# followers_v1.net
KiCad netlist of a schematic drawn in EAGLE
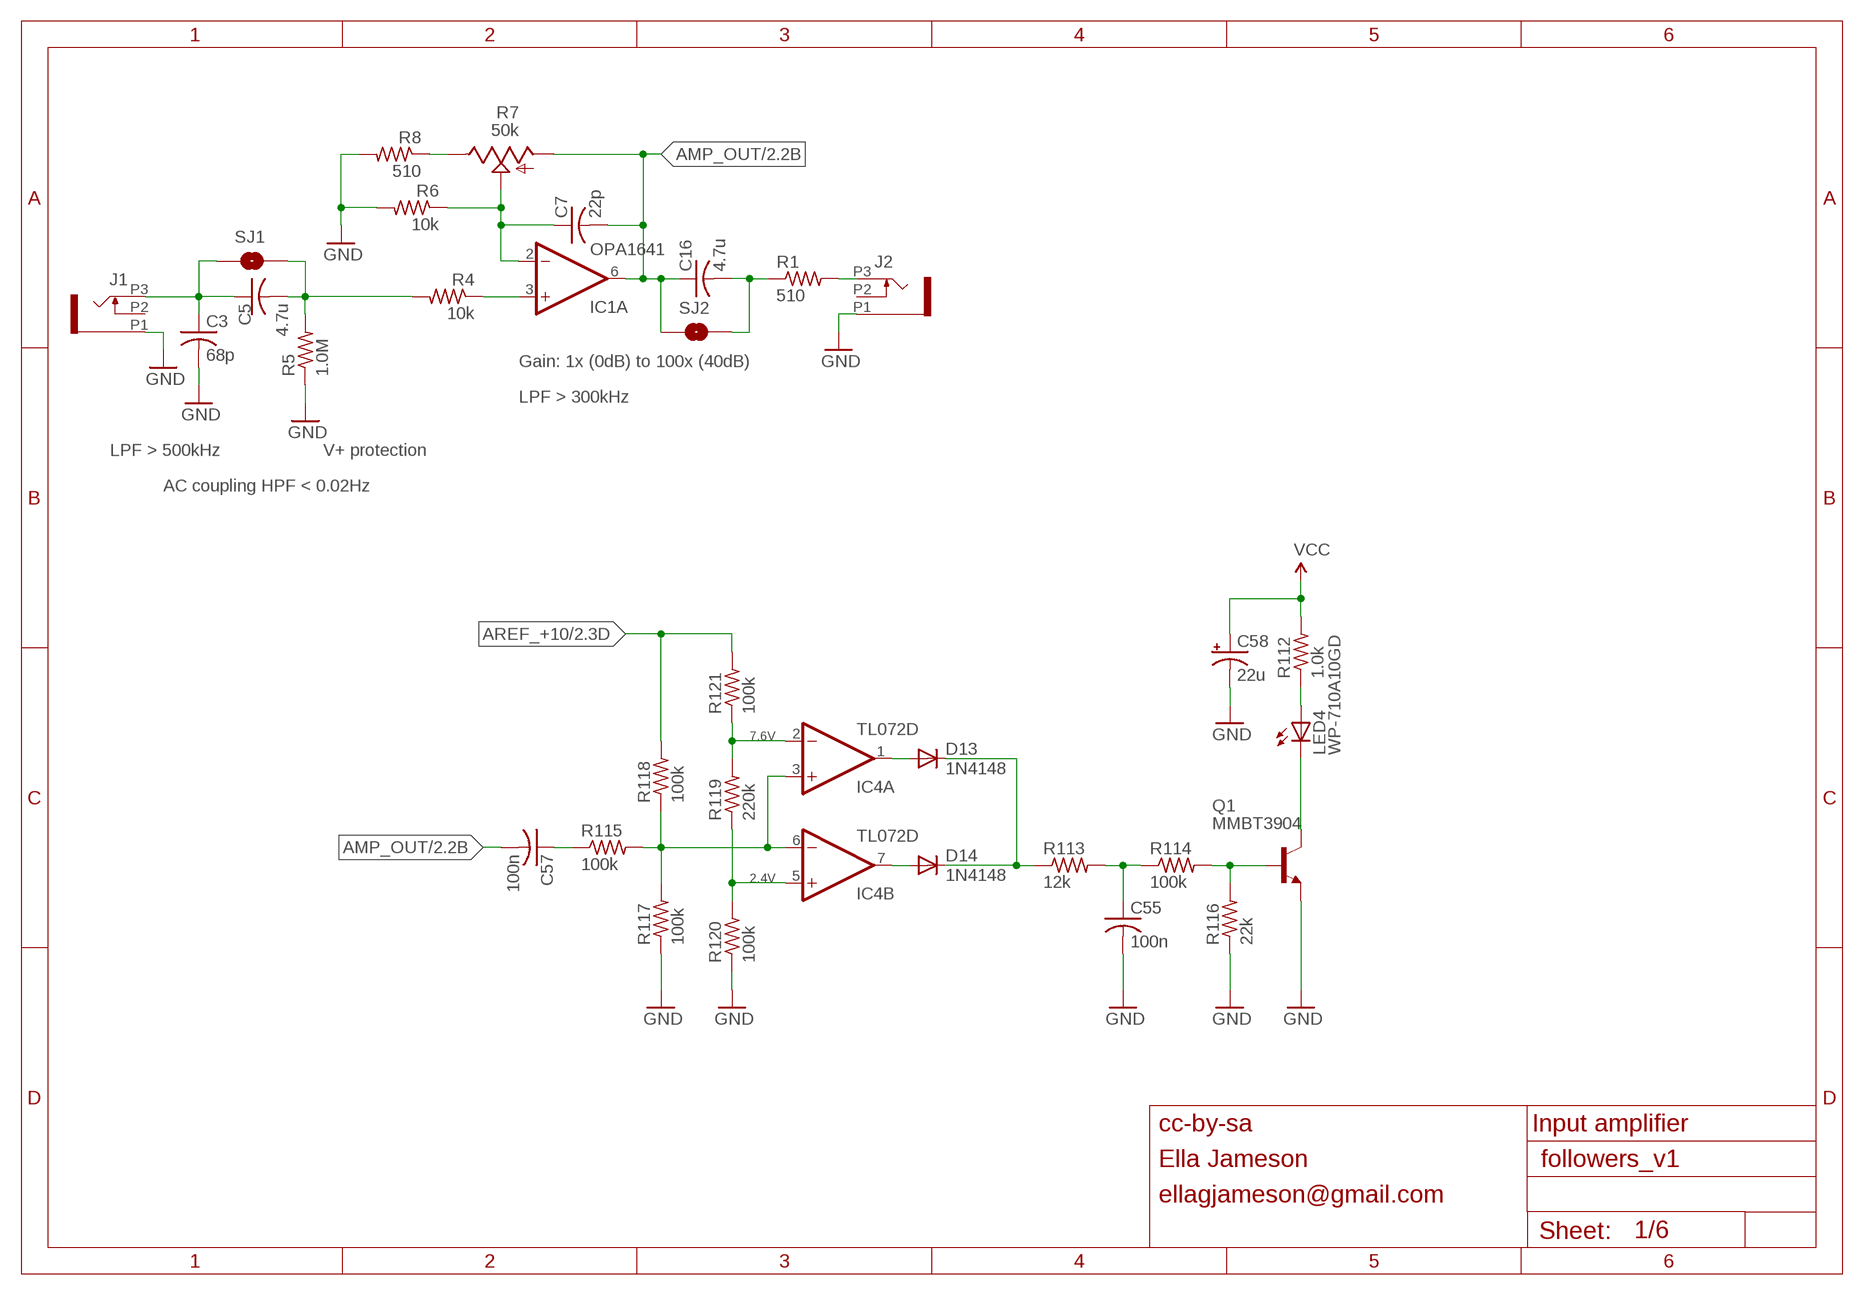
[diagram p0: schematic, sheet 1]
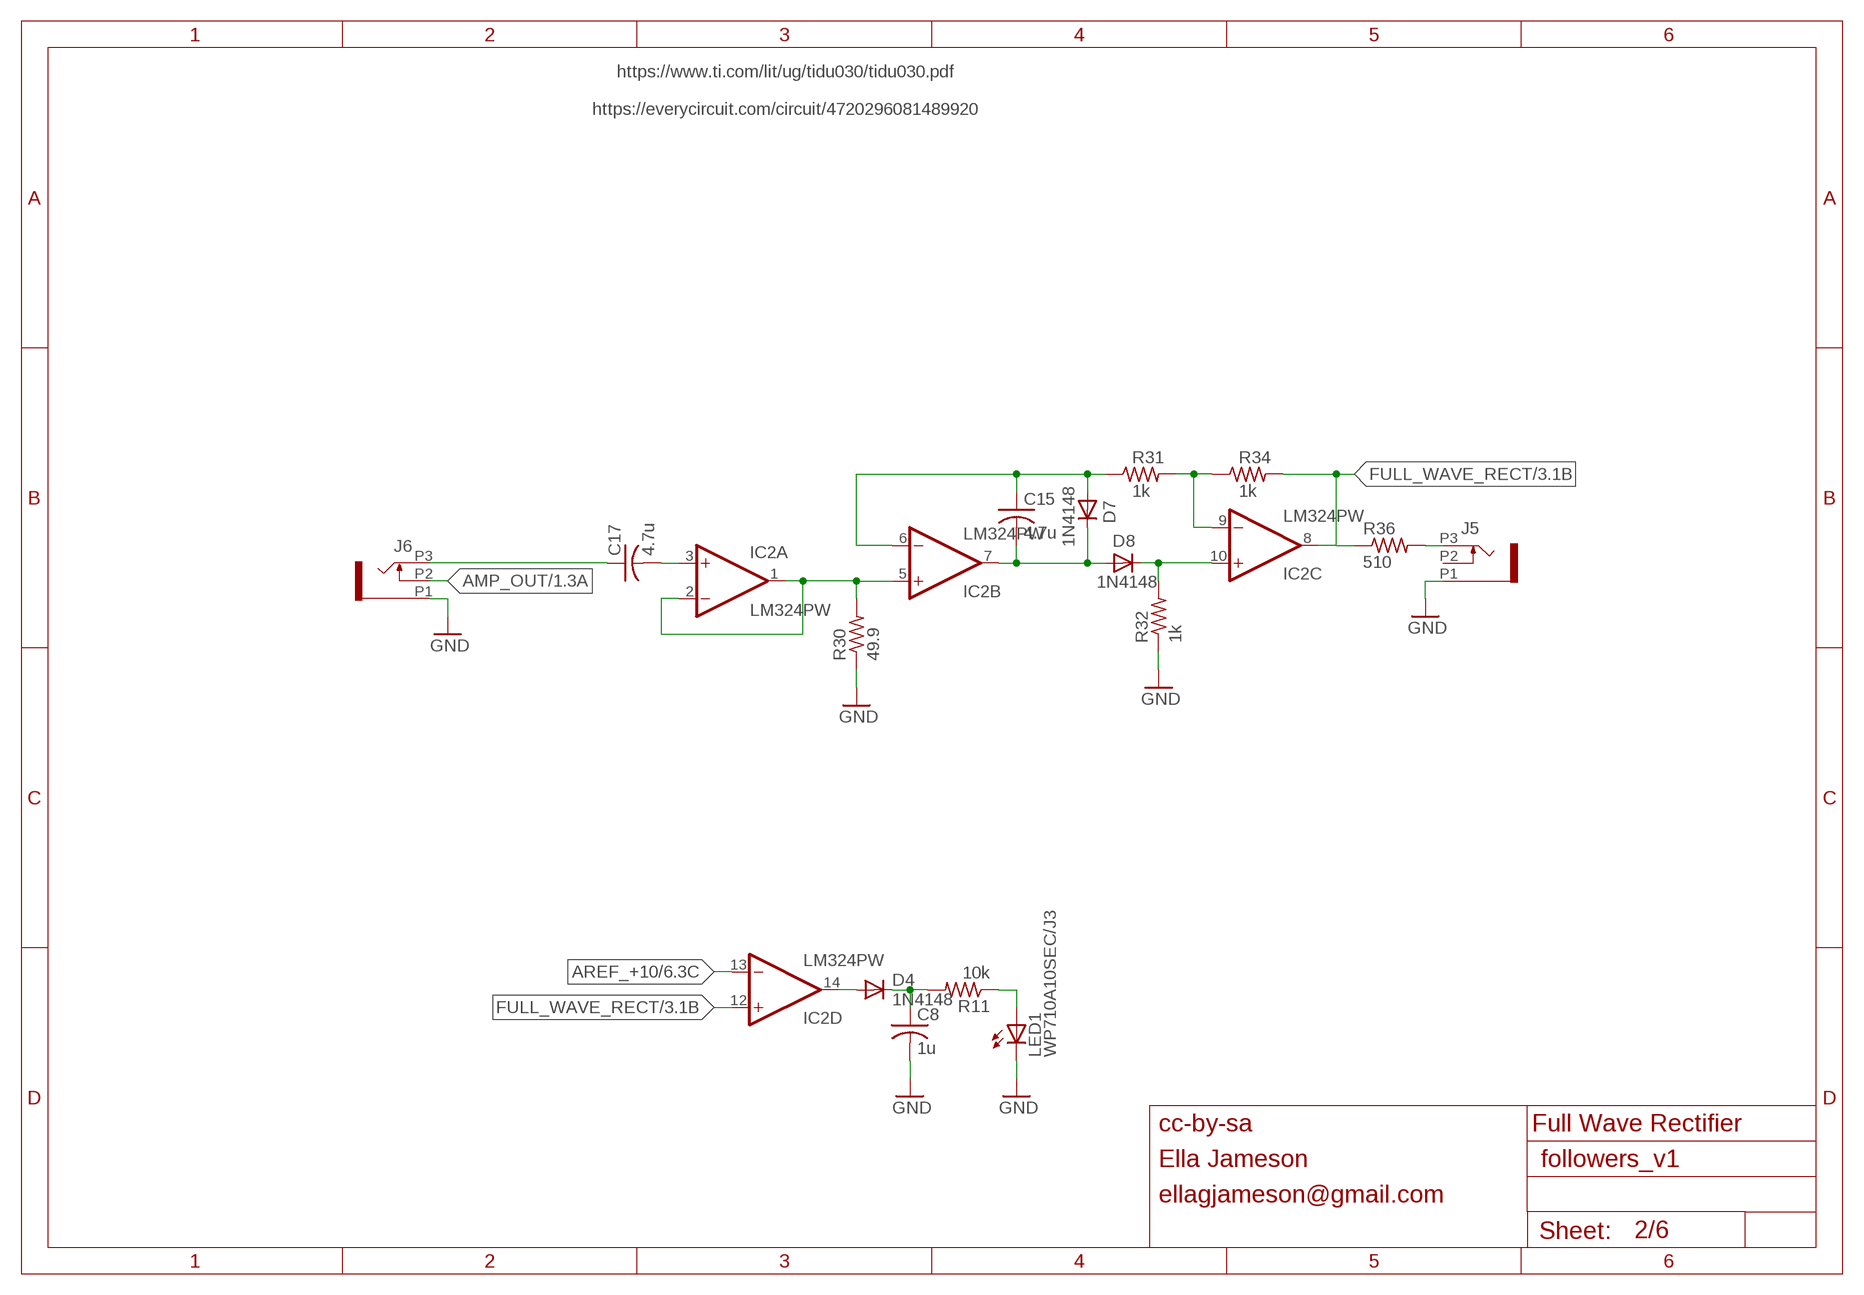
[diagram p1: schematic, sheet 2]
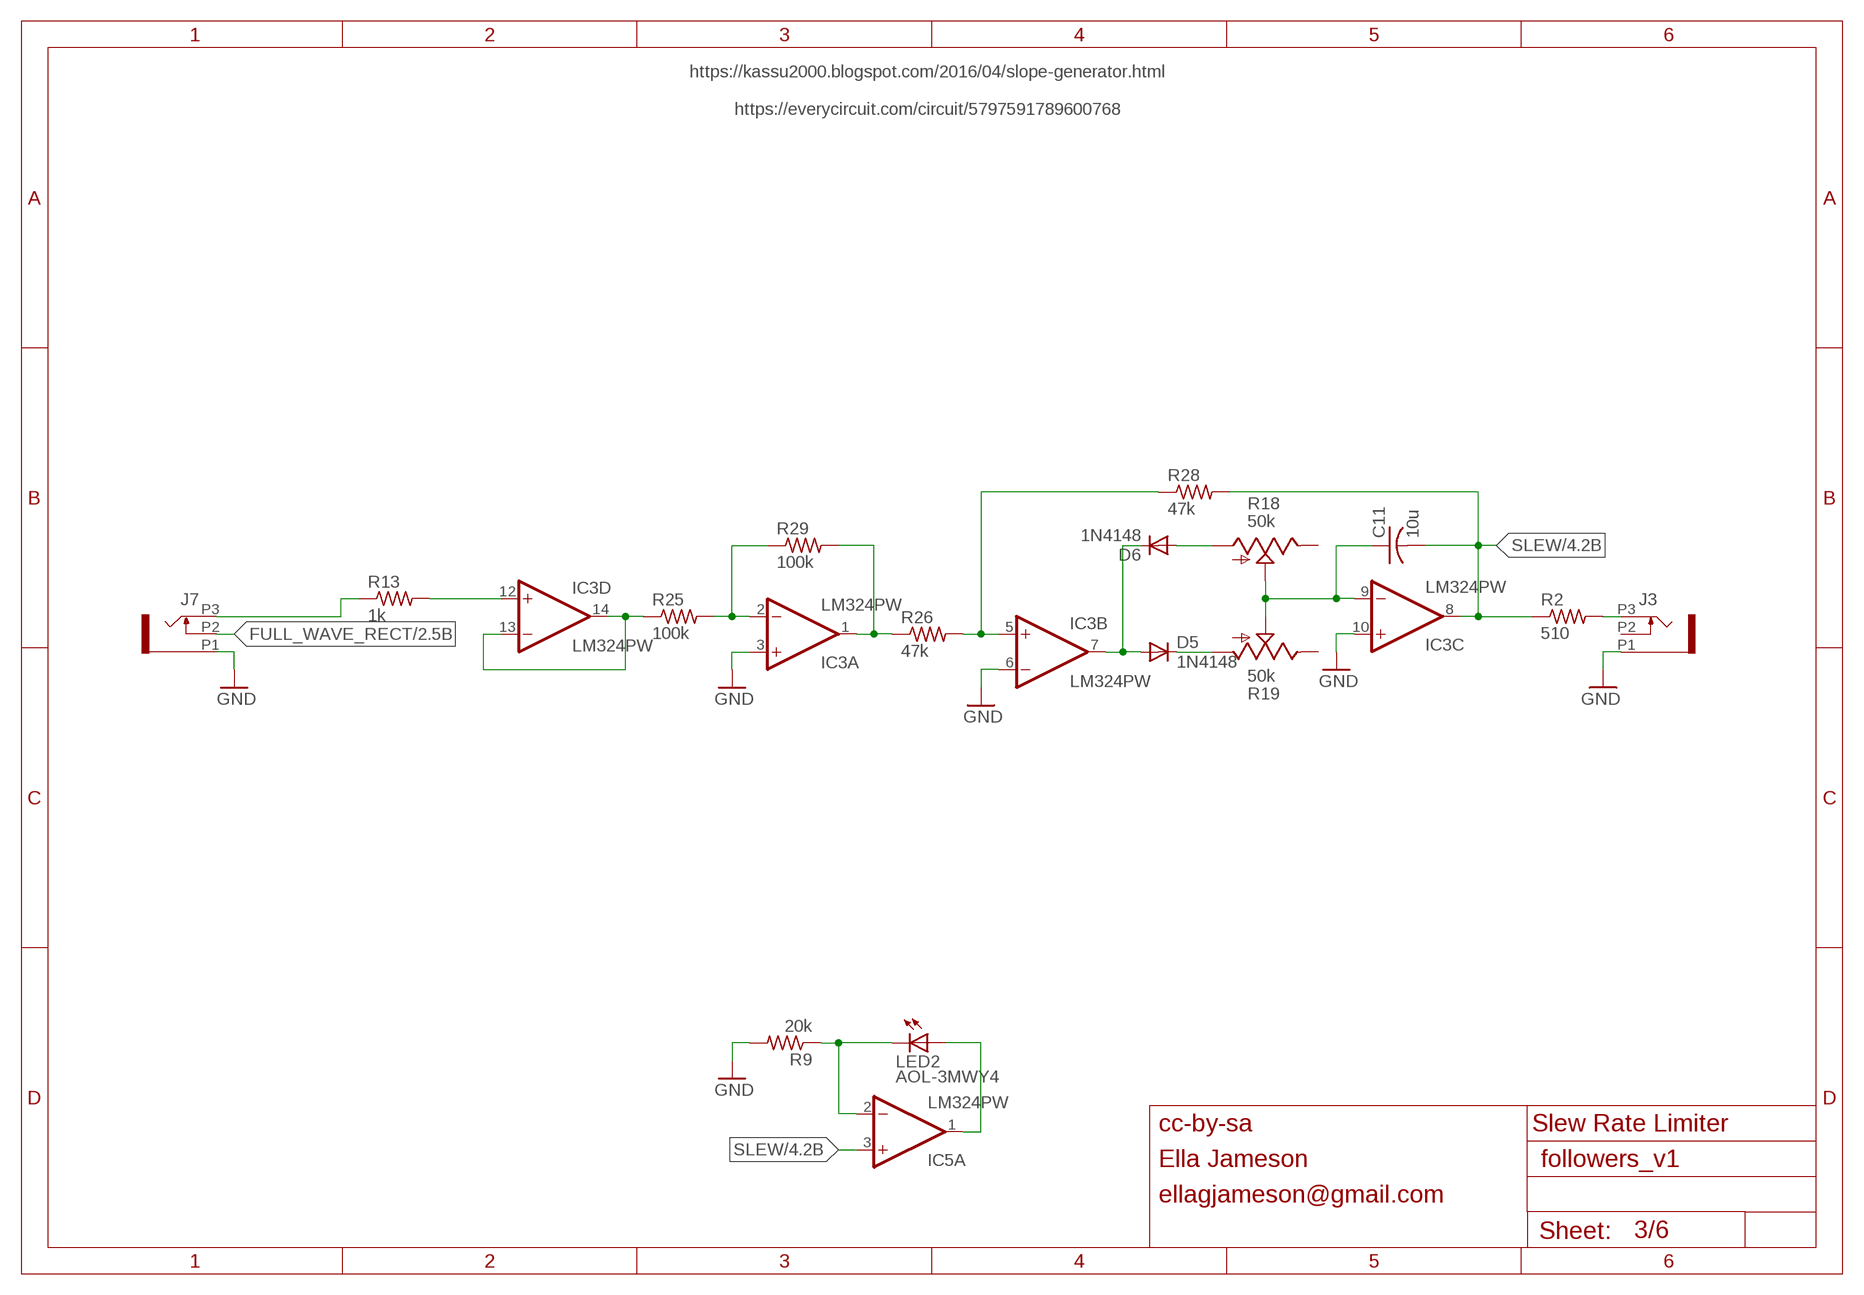
[diagram p2: schematic, sheet 3]
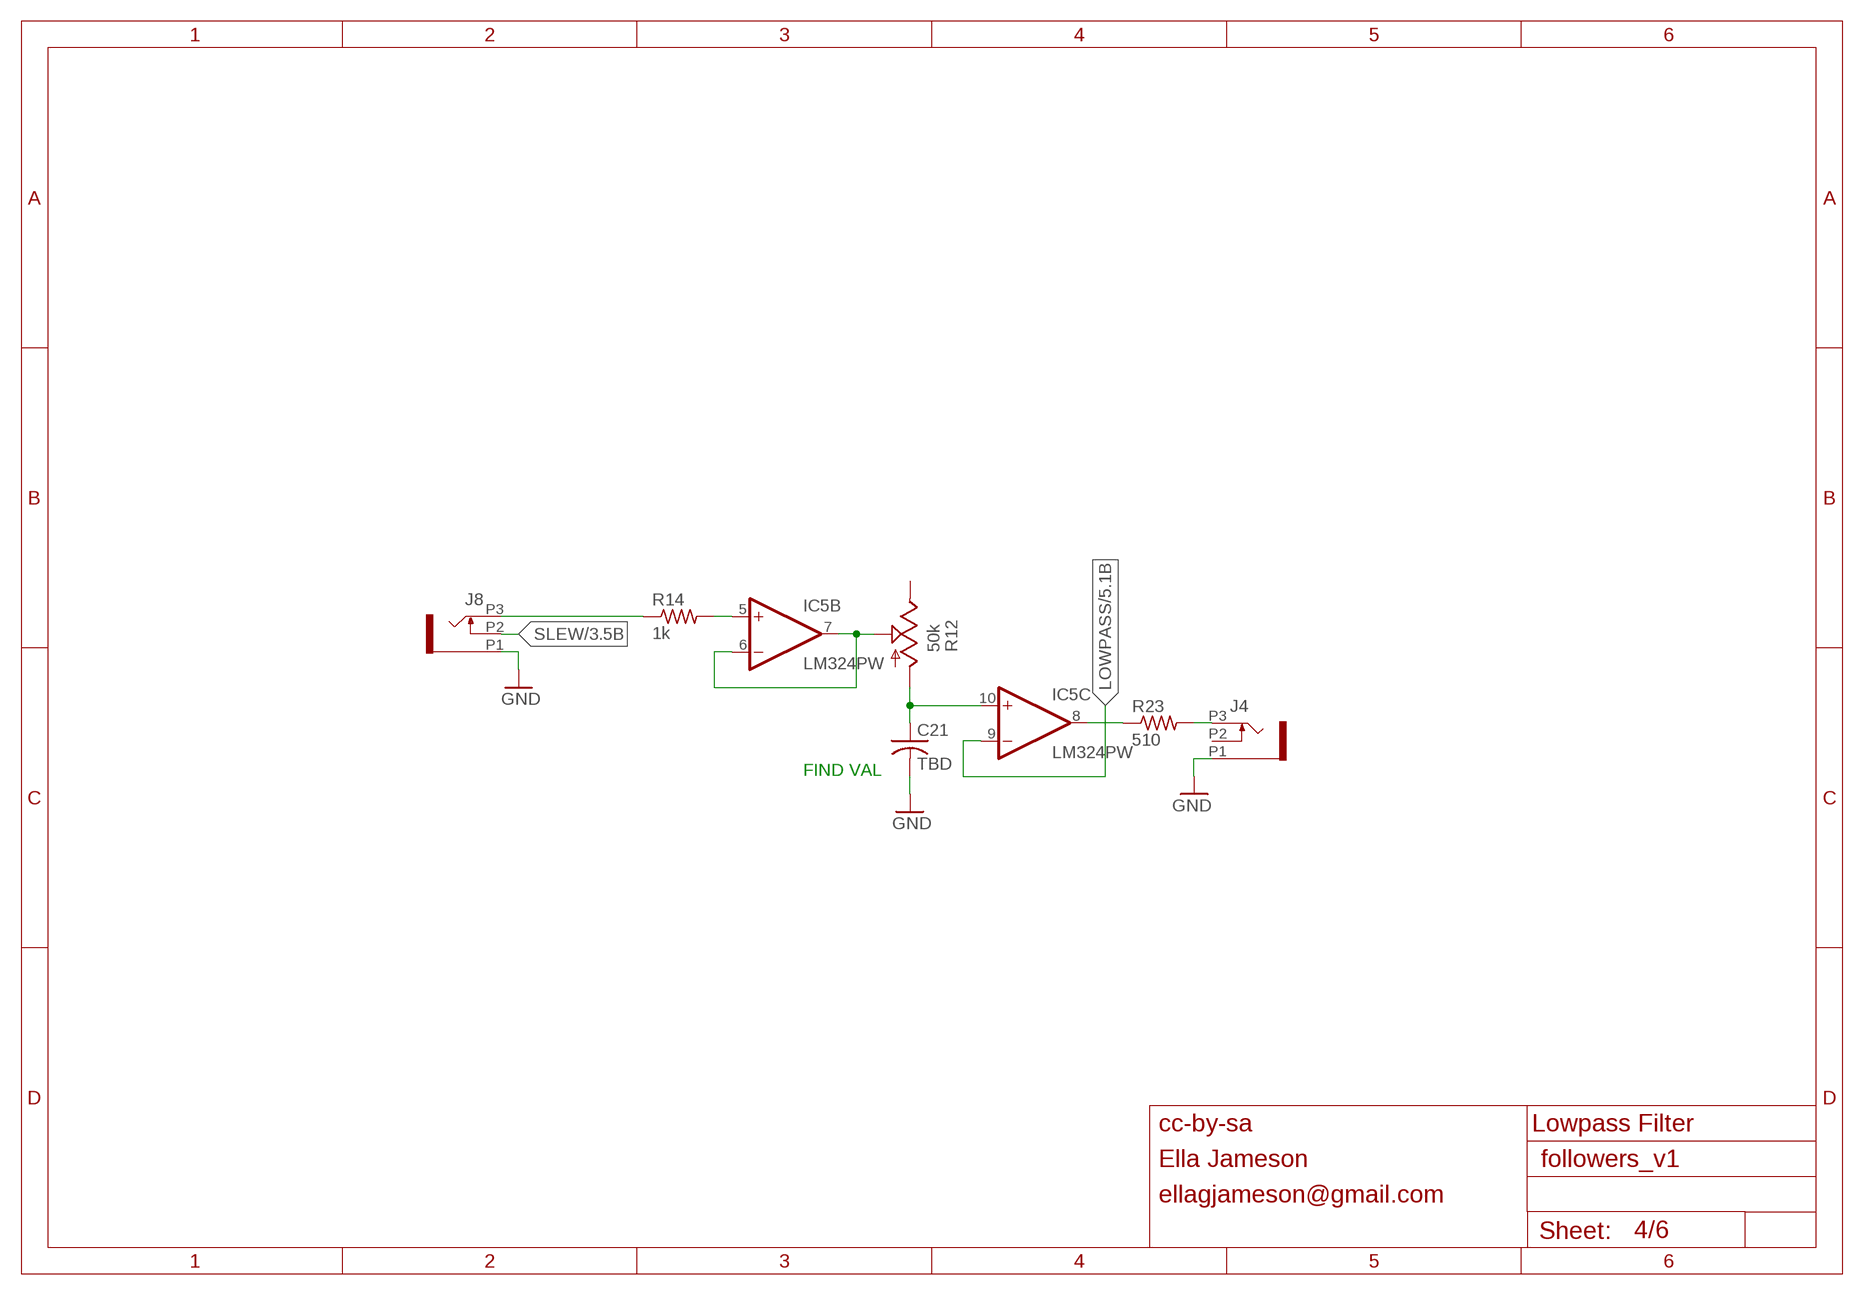
[diagram p3: schematic, sheet 4]
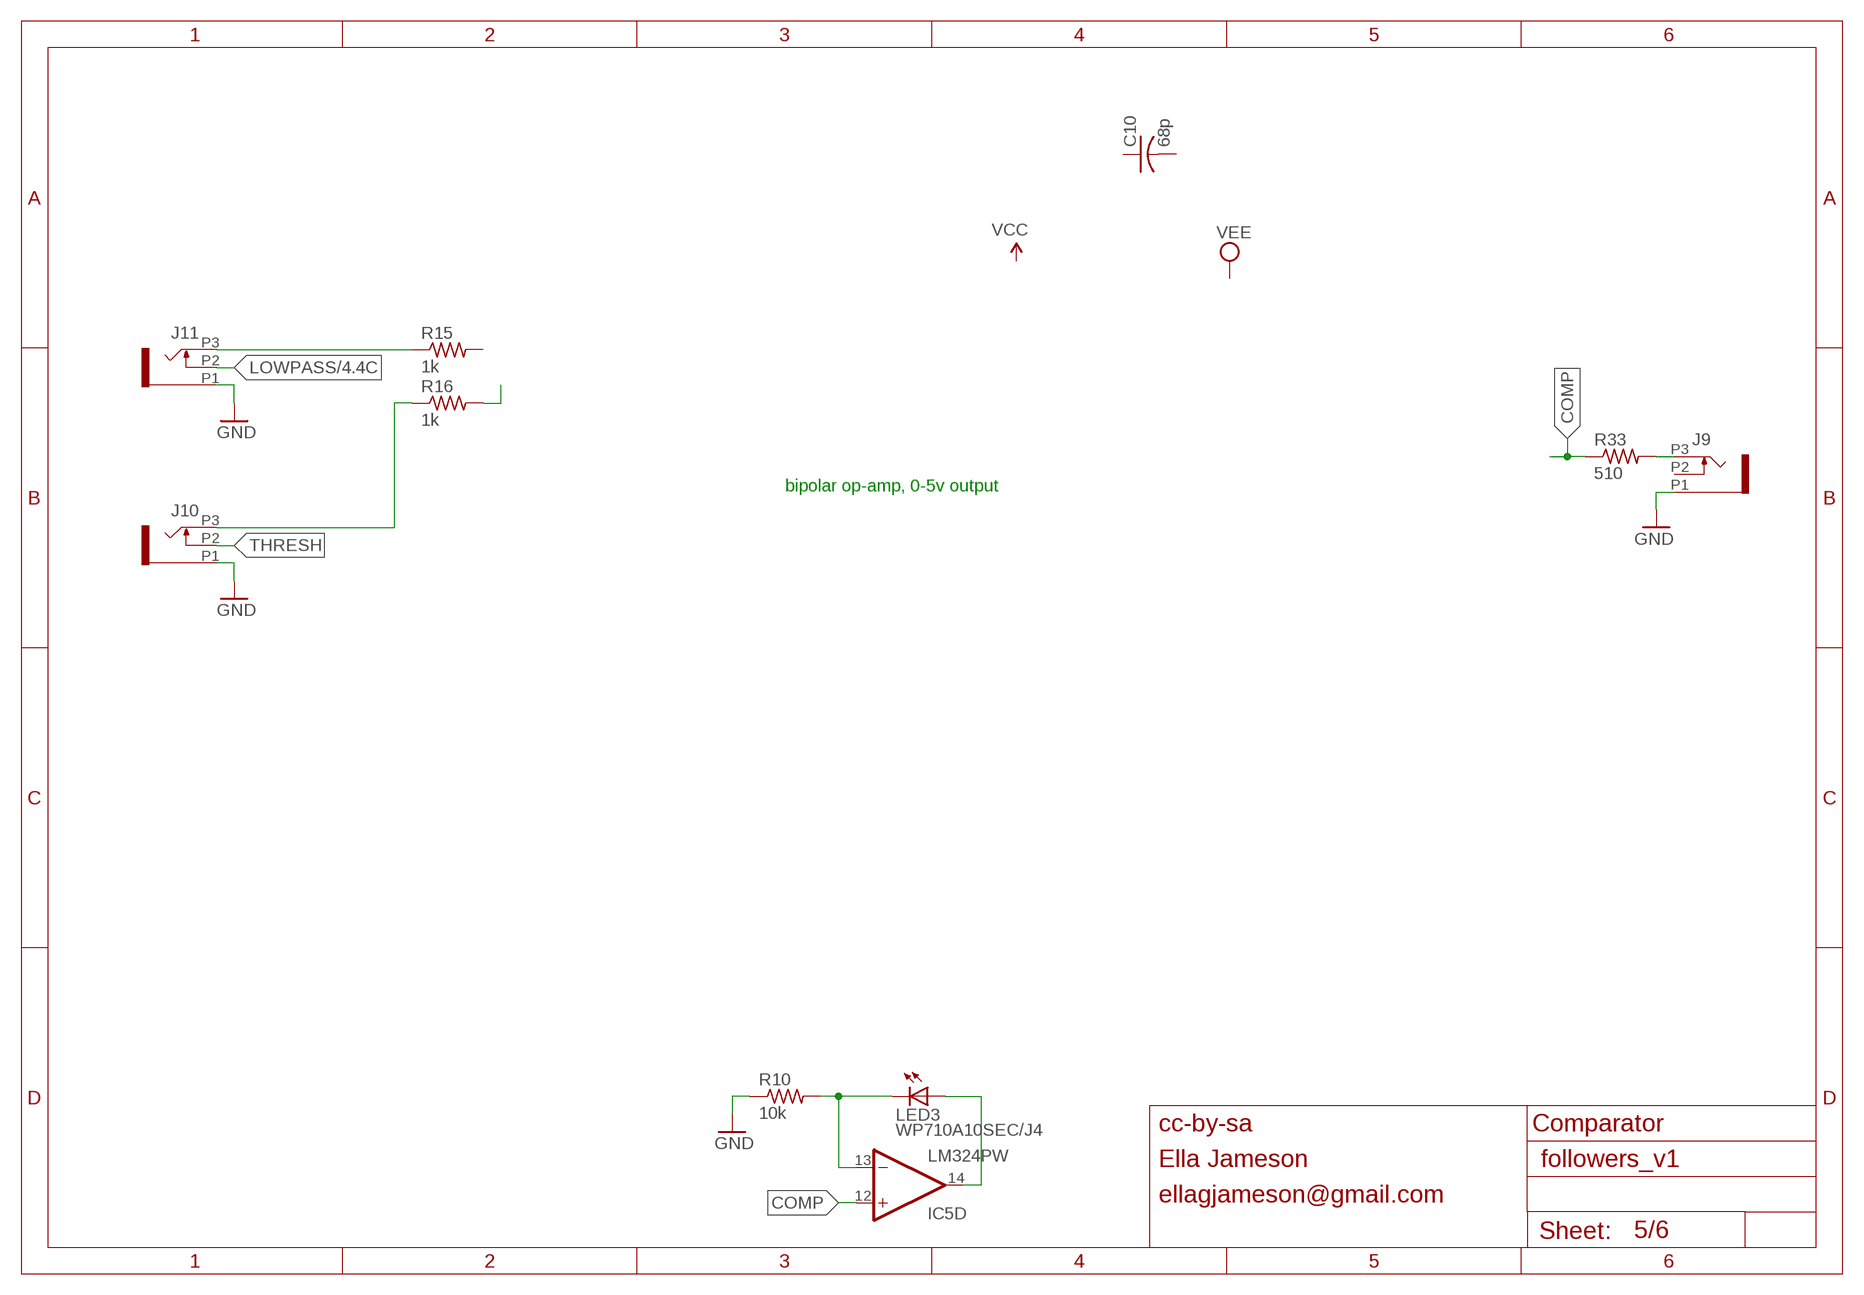
[diagram p4: schematic, sheet 5]
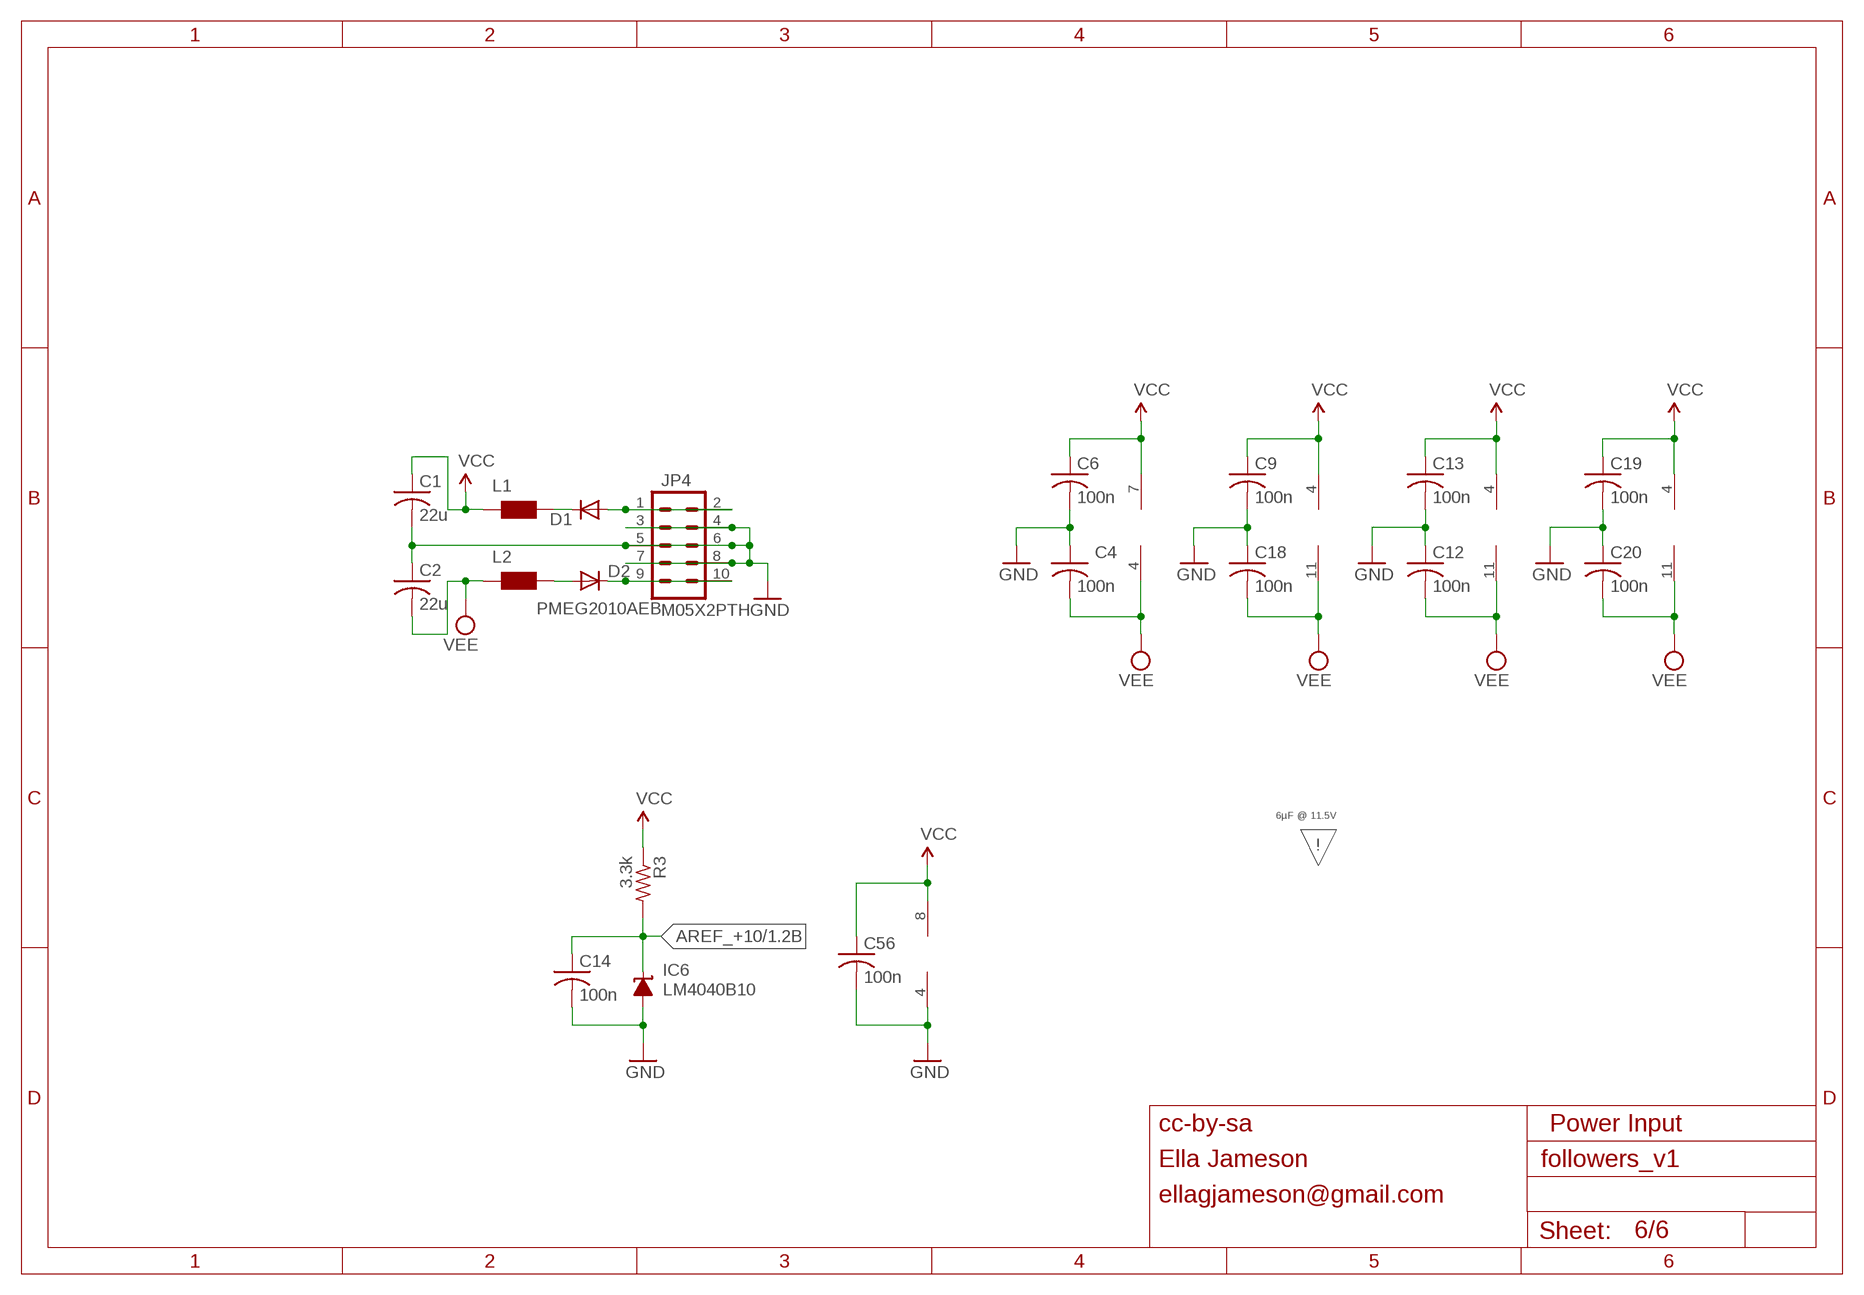
[diagram p5: schematic, sheet 6]

(export (version "E")
  (design (tool "Eeschema 10.0.6"))
  (components
    (comp (ref "C11")
      (value "10u")
      (footprint "eagle-import:C0402")
      (libsource (lib "eagle-import") (part "C-USC0402"))
    )
    (comp (ref "D5")
      (value "1N4148")
      (footprint "eagle-import:SOD523")
      (libsource (lib "eagle-import") (part "DIODE-SOD523"))
    )
    (comp (ref "D6")
      (value "1N4148")
      (footprint "eagle-import:SOD523")
      (libsource (lib "eagle-import") (part "DIODE-SOD523"))
    )
    (comp (ref "IC3")
      (value "LM324PW")
      (footprint "eagle-import:TSSOP14")
      (libsource (lib "eagle-import") (part "LM324PW"))
    )
    (comp (ref "IC5")
      (value "LM324PW")
      (footprint "eagle-import:TSSOP14")
      (libsource (lib "eagle-import") (part "LM324PW"))
    )
    (comp (ref "J3")
      (value "PJ301_THONKICONN6")
      (footprint "eagle-import:WQP_PJ_301M6")
      (libsource (lib "eagle-import") (part "PJ301_THONKICONN6"))
    )
    (comp (ref "J7")
      (value "PJ301_THONKICONN6")
      (footprint "eagle-import:WQP_PJ_301M6")
      (libsource (lib "eagle-import") (part "PJ301_THONKICONN6"))
    )
    (comp (ref "LED2")
      (value "AOL-3MWY4")
      (footprint "eagle-import:LED3MM")
      (libsource (lib "eagle-import") (part "LED3MM"))
    )
    (comp (ref "R2")
      (value "510")
      (footprint "eagle-import:R0402")
      (libsource (lib "eagle-import") (part "R-US_R0402"))
    )
    (comp (ref "R9")
      (value "20k")
      (footprint "eagle-import:R0402")
      (libsource (lib "eagle-import") (part "R-US_R0402"))
    )
    (comp (ref "R13")
      (value "1k")
      (footprint "eagle-import:R0402")
      (libsource (lib "eagle-import") (part "R-US_R0402"))
    )
    (comp (ref "R18")
      (value "50k")
      (footprint "eagle-import:ALPS_POT_VERTICAL_PS")
      (libsource (lib "eagle-import") (part "POT_USVERTICAL_PS"))
    )
    (comp (ref "R19")
      (value "50k")
      (footprint "eagle-import:ALPS_POT_VERTICAL_PS")
      (libsource (lib "eagle-import") (part "POT_USVERTICAL_PS"))
    )
    (comp (ref "R25")
      (value "100k")
      (footprint "eagle-import:R0402")
      (libsource (lib "eagle-import") (part "R-US_R0402"))
    )
    (comp (ref "R26")
      (value "47k")
      (footprint "eagle-import:R0402")
      (libsource (lib "eagle-import") (part "R-US_R0402"))
    )
    (comp (ref "R28")
      (value "47k")
      (footprint "eagle-import:R0402")
      (libsource (lib "eagle-import") (part "R-US_R0402"))
    )
    (comp (ref "R29")
      (value "100k")
      (footprint "eagle-import:R0402")
      (libsource (lib "eagle-import") (part "R-US_R0402"))
    )
    (comp (ref "C21")
      (value "TBD")
      (footprint "eagle-import:C0402")
      (libsource (lib "eagle-import") (part "C-USC0402"))
    )
    (comp (ref "J4")
      (value "PJ301_THONKICONN6")
      (footprint "eagle-import:WQP_PJ_301M6")
      (libsource (lib "eagle-import") (part "PJ301_THONKICONN6"))
    )
    (comp (ref "J8")
      (value "PJ301_THONKICONN6")
      (footprint "eagle-import:WQP_PJ_301M6")
      (libsource (lib "eagle-import") (part "PJ301_THONKICONN6"))
    )
    (comp (ref "R12")
      (value "50k")
      (footprint "eagle-import:ALPS_POT_VERTICAL_PS")
      (libsource (lib "eagle-import") (part "POT_USVERTICAL_PS"))
    )
    (comp (ref "R14")
      (value "1k")
      (footprint "eagle-import:R0402")
      (libsource (lib "eagle-import") (part "R-US_R0402"))
    )
    (comp (ref "R23")
      (value "510")
      (footprint "eagle-import:R0402")
      (libsource (lib "eagle-import") (part "R-US_R0402"))
    )
    (comp (ref "C1")
      (value "22u")
      (footprint "eagle-import:C1206")
      (libsource (lib "eagle-import") (part "C-USC1206"))
    )
    (comp (ref "C2")
      (value "22u")
      (footprint "eagle-import:C1206")
      (libsource (lib "eagle-import") (part "C-USC1206"))
    )
    (comp (ref "C4")
      (value "100n")
      (footprint "eagle-import:C0402")
      (libsource (lib "eagle-import") (part "C-USC0402"))
    )
    (comp (ref "C6")
      (value "100n")
      (footprint "eagle-import:C0402")
      (libsource (lib "eagle-import") (part "C-USC0402"))
    )
    (comp (ref "C9")
      (value "100n")
      (footprint "eagle-import:C0402")
      (libsource (lib "eagle-import") (part "C-USC0402"))
    )
    (comp (ref "C12")
      (value "100n")
      (footprint "eagle-import:C0402")
      (libsource (lib "eagle-import") (part "C-USC0402"))
    )
    (comp (ref "C13")
      (value "100n")
      (footprint "eagle-import:C0402")
      (libsource (lib "eagle-import") (part "C-USC0402"))
    )
    (comp (ref "C14")
      (value "100n")
      (footprint "eagle-import:C0603")
      (libsource (lib "eagle-import") (part "C-USC0603"))
    )
    (comp (ref "C18")
      (value "100n")
      (footprint "eagle-import:C0402")
      (libsource (lib "eagle-import") (part "C-USC0402"))
    )
    (comp (ref "C19")
      (value "100n")
      (footprint "eagle-import:C0402")
      (libsource (lib "eagle-import") (part "C-USC0402"))
    )
    (comp (ref "C20")
      (value "100n")
      (footprint "eagle-import:C0402")
      (libsource (lib "eagle-import") (part "C-USC0402"))
    )
    (comp (ref "C56")
      (value "100n")
      (footprint "eagle-import:C0603")
      (libsource (lib "eagle-import") (part "C-USC0603"))
    )
    (comp (ref "D1")
      (value "PMEG2010AEB")
      (footprint "eagle-import:SOD523")
      (libsource (lib "eagle-import") (part "DIODE-SOD523"))
    )
    (comp (ref "D2")
      (value "PMEG2010AEB")
      (footprint "eagle-import:SOD523")
      (libsource (lib "eagle-import") (part "DIODE-SOD523"))
    )
    (comp (ref "IC1")
      (value "OPA1641")
      (footprint "eagle-import:MSOP8")
      (libsource (lib "eagle-import") (part "OPA1641"))
    )
    (comp (ref "IC2")
      (value "LM324PW")
      (footprint "eagle-import:TSSOP14")
      (libsource (lib "eagle-import") (part "LM324PW"))
    )
    (comp (ref "IC4")
      (value "TL072D")
      (footprint "eagle-import:SO08")
      (libsource (lib "eagle-import") (part "TL072D"))
    )
    (comp (ref "IC6")
      (value "LM4040B10")
      (footprint "eagle-import:DBZ_R-PDSO-G3")
      (libsource (lib "eagle-import") (part "LM4041DBZB12"))
    )
    (comp (ref "JP4")
      (value "M05X2PTH")
      (footprint "eagle-import:AVR_ICSP")
      (libsource (lib "eagle-import") (part "M05X2PTH"))
    )
    (comp (ref "L1")
      (value "WE-CBF_0603")
      (footprint "eagle-import:0603")
      (libsource (lib "eagle-import") (part "WE-CBF_0603"))
    )
    (comp (ref "L2")
      (value "WE-CBF_0603")
      (footprint "eagle-import:0603")
      (libsource (lib "eagle-import") (part "WE-CBF_0603"))
    )
    (comp (ref "R3")
      (value "3.3k")
      (footprint "eagle-import:R0603")
      (libsource (lib "eagle-import") (part "R-US_R0603"))
    )
    (comp (ref "C10")
      (value "68p")
      (footprint "eagle-import:C0402")
      (libsource (lib "eagle-import") (part "C-USC0402"))
    )
    (comp (ref "J9")
      (value "PJ301_THONKICONN6")
      (footprint "eagle-import:WQP_PJ_301M6")
      (libsource (lib "eagle-import") (part "PJ301_THONKICONN6"))
    )
    (comp (ref "J10")
      (value "PJ301_THONKICONN6")
      (footprint "eagle-import:WQP_PJ_301M6")
      (libsource (lib "eagle-import") (part "PJ301_THONKICONN6"))
    )
    (comp (ref "J11")
      (value "PJ301_THONKICONN6")
      (footprint "eagle-import:WQP_PJ_301M6")
      (libsource (lib "eagle-import") (part "PJ301_THONKICONN6"))
    )
    (comp (ref "LED3")
      (value "WP710A10SEC/J4")
      (footprint "eagle-import:LED3MM")
      (libsource (lib "eagle-import") (part "LED3MM"))
    )
    (comp (ref "R10")
      (value "10k")
      (footprint "eagle-import:R0402")
      (libsource (lib "eagle-import") (part "R-US_R0402"))
    )
    (comp (ref "R15")
      (value "1k")
      (footprint "eagle-import:R0402")
      (libsource (lib "eagle-import") (part "R-US_R0402"))
    )
    (comp (ref "R16")
      (value "1k")
      (footprint "eagle-import:R0402")
      (libsource (lib "eagle-import") (part "R-US_R0402"))
    )
    (comp (ref "R33")
      (value "510")
      (footprint "eagle-import:R0402")
      (libsource (lib "eagle-import") (part "R-US_R0402"))
    )
    (comp (ref "C3")
      (value "68p")
      (footprint "eagle-import:C0402")
      (libsource (lib "eagle-import") (part "C-USC0402"))
    )
    (comp (ref "C5")
      (value "4.7u")
      (footprint "eagle-import:C0603")
      (libsource (lib "eagle-import") (part "C-USC0603"))
    )
    (comp (ref "C7")
      (value "22p")
      (footprint "eagle-import:C0402")
      (libsource (lib "eagle-import") (part "C-USC0402"))
    )
    (comp (ref "C16")
      (value "4.7u")
      (footprint "eagle-import:C0603")
      (libsource (lib "eagle-import") (part "C-USC0603"))
    )
    (comp (ref "C55")
      (value "100n")
      (footprint "eagle-import:C0603")
      (libsource (lib "eagle-import") (part "C-USC0603"))
    )
    (comp (ref "C57")
      (value "100n")
      (footprint "eagle-import:C0603")
      (libsource (lib "eagle-import") (part "C-USC0603"))
    )
    (comp (ref "C58")
      (value "22u")
      (footprint "eagle-import:PANASONIC_C")
      (libsource (lib "eagle-import") (part "CPOL-USC"))
    )
    (comp (ref "D13")
      (value "1N4148")
      (footprint "eagle-import:SOD323-W")
      (libsource (lib "eagle-import") (part "DIODE-SOD323-W"))
    )
    (comp (ref "D14")
      (value "1N4148")
      (footprint "eagle-import:SOD323-W")
      (libsource (lib "eagle-import") (part "DIODE-SOD323-W"))
    )
    (comp (ref "J1")
      (value "PJ301_THONKICONN6")
      (footprint "eagle-import:WQP_PJ_301M6")
      (libsource (lib "eagle-import") (part "PJ301_THONKICONN6"))
    )
    (comp (ref "J2")
      (value "PJ301_THONKICONN6")
      (footprint "eagle-import:WQP_PJ_301M6")
      (libsource (lib "eagle-import") (part "PJ301_THONKICONN6"))
    )
    (comp (ref "LED4")
      (value "WP-710A10GD")
      (footprint "eagle-import:LED3MM")
      (libsource (lib "eagle-import") (part "LED3MM"))
    )
    (comp (ref "Q1")
      (value "MMBT3904")
      (footprint "eagle-import:SOT23-BEC")
      (libsource (lib "eagle-import") (part "-NPN-SOT23-BECMMBT3904LT1"))
    )
    (comp (ref "R1")
      (value "510")
      (footprint "eagle-import:R0402")
      (libsource (lib "eagle-import") (part "R-US_R0402"))
    )
    (comp (ref "R4")
      (value "10k")
      (footprint "eagle-import:R0402")
      (libsource (lib "eagle-import") (part "R-US_R0402"))
    )
    (comp (ref "R5")
      (value "1.0M")
      (footprint "eagle-import:R0402")
      (libsource (lib "eagle-import") (part "R-US_R0402"))
    )
    (comp (ref "R6")
      (value "10k")
      (footprint "eagle-import:R0402")
      (libsource (lib "eagle-import") (part "R-US_R0402"))
    )
    (comp (ref "R7")
      (value "50k")
      (footprint "eagle-import:ALPS_POT_VERTICAL_PS")
      (libsource (lib "eagle-import") (part "POT_USVERTICAL_PS"))
    )
    (comp (ref "R8")
      (value "510")
      (footprint "eagle-import:R0402")
      (libsource (lib "eagle-import") (part "R-US_R0402"))
    )
    (comp (ref "R112")
      (value "1.0k")
      (footprint "eagle-import:R0603")
      (libsource (lib "eagle-import") (part "R-US_R0603"))
    )
    (comp (ref "R113")
      (value "12k")
      (footprint "eagle-import:R0603")
      (libsource (lib "eagle-import") (part "R-US_R0603"))
    )
    (comp (ref "R114")
      (value "100k")
      (footprint "eagle-import:R0603")
      (libsource (lib "eagle-import") (part "R-US_R0603"))
    )
    (comp (ref "R115")
      (value "100k")
      (footprint "eagle-import:R0603")
      (libsource (lib "eagle-import") (part "R-US_R0603"))
    )
    (comp (ref "R116")
      (value "22k")
      (footprint "eagle-import:R0603")
      (libsource (lib "eagle-import") (part "R-US_R0603"))
    )
    (comp (ref "R117")
      (value "100k")
      (footprint "eagle-import:R0603")
      (libsource (lib "eagle-import") (part "R-US_R0603"))
    )
    (comp (ref "R118")
      (value "100k")
      (footprint "eagle-import:R0603")
      (libsource (lib "eagle-import") (part "R-US_R0603"))
    )
    (comp (ref "R119")
      (value "220k")
      (footprint "eagle-import:R0603")
      (libsource (lib "eagle-import") (part "R-US_R0603"))
    )
    (comp (ref "R120")
      (value "100k")
      (footprint "eagle-import:R0603")
      (libsource (lib "eagle-import") (part "R-US_R0603"))
    )
    (comp (ref "R121")
      (value "100k")
      (footprint "eagle-import:R0603")
      (libsource (lib "eagle-import") (part "R-US_R0603"))
    )
    (comp (ref "SJ1")
      (value "SOLDERJUMPERNC")
      (footprint "eagle-import:SJ_2S")
      (libsource (lib "eagle-import") (part "SOLDERJUMPERNC"))
    )
    (comp (ref "SJ2")
      (value "SOLDERJUMPERNC")
      (footprint "eagle-import:SJ_2S")
      (libsource (lib "eagle-import") (part "SOLDERJUMPERNC"))
    )
    (comp (ref "C8")
      (value "1u")
      (footprint "eagle-import:C0402")
      (libsource (lib "eagle-import") (part "C-USC0402"))
    )
    (comp (ref "C15")
      (value "4.7u")
      (footprint "eagle-import:C0603")
      (libsource (lib "eagle-import") (part "C-USC0603"))
    )
    (comp (ref "C17")
      (value "4.7u")
      (footprint "eagle-import:C0603")
      (libsource (lib "eagle-import") (part "C-USC0603"))
    )
    (comp (ref "D4")
      (value "1N4148")
      (footprint "eagle-import:SOD523")
      (libsource (lib "eagle-import") (part "DIODE-SOD523"))
    )
    (comp (ref "D7")
      (value "1N4148")
      (footprint "eagle-import:SOD523")
      (libsource (lib "eagle-import") (part "DIODE-SOD523"))
    )
    (comp (ref "D8")
      (value "1N4148")
      (footprint "eagle-import:SOD523")
      (libsource (lib "eagle-import") (part "DIODE-SOD523"))
    )
    (comp (ref "J5")
      (value "PJ301_THONKICONN6")
      (footprint "eagle-import:WQP_PJ_301M6")
      (libsource (lib "eagle-import") (part "PJ301_THONKICONN6"))
    )
    (comp (ref "J6")
      (value "PJ301_THONKICONN6")
      (footprint "eagle-import:WQP_PJ_301M6")
      (libsource (lib "eagle-import") (part "PJ301_THONKICONN6"))
    )
    (comp (ref "LED1")
      (value "WP710A10SEC/J3")
      (footprint "eagle-import:LED3MM")
      (libsource (lib "eagle-import") (part "LED3MM"))
    )
    (comp (ref "R11")
      (value "10k")
      (footprint "eagle-import:R0402")
      (libsource (lib "eagle-import") (part "R-US_R0402"))
    )
    (comp (ref "R30")
      (value "49.9")
      (footprint "eagle-import:R0402")
      (libsource (lib "eagle-import") (part "R-US_R0402"))
    )
    (comp (ref "R31")
      (value "1k")
      (footprint "eagle-import:R0402")
      (libsource (lib "eagle-import") (part "R-US_R0402"))
    )
    (comp (ref "R32")
      (value "1k")
      (footprint "eagle-import:R0402")
      (libsource (lib "eagle-import") (part "R-US_R0402"))
    )
    (comp (ref "R34")
      (value "1k")
      (footprint "eagle-import:R0402")
      (libsource (lib "eagle-import") (part "R-US_R0402"))
    )
    (comp (ref "R36")
      (value "510")
      (footprint "eagle-import:R0402")
      (libsource (lib "eagle-import") (part "R-US_R0402"))
    )
  )
  (nets
    (net (code "1") (name "AMP_OUT") (class "Default")
      (node (ref "C16") (pin "1") (pinfunction "1_1") (pintype "passive"))
      (node (ref "C57") (pin "2") (pinfunction "2_2") (pintype "passive"))
      (node (ref "C7") (pin "2") (pinfunction "2_2") (pintype "passive"))
      (node (ref "IC1") (pin "6") (pinfunction "OUT_6") (pintype "output"))
      (node (ref "J6") (pin "P2") (pinfunction "2_P2") (pintype "passive"))
      (node (ref "R7") (pin "P$3") (pinfunction "A_P$3") (pintype "passive"))
      (node (ref "SJ2") (pin "1") (pinfunction "1_1") (pintype "passive"))
    )
    (net (code "2") (name "AREF_+10") (class "Default")
      (node (ref "C14") (pin "1") (pinfunction "1_1") (pintype "passive"))
      (node (ref "IC2") (pin "13") (pinfunction "-IN_13") (pintype "input"))
      (node (ref "IC6") (pin "1") (pinfunction "C_1") (pintype "passive"))
      (node (ref "R118") (pin "2") (pinfunction "2_2") (pintype "passive"))
      (node (ref "R121") (pin "2") (pinfunction "2_2") (pintype "passive"))
      (node (ref "R3") (pin "2") (pinfunction "2_2") (pintype "passive"))
    )
    (net (code "3") (name "COMP") (class "Default")
      (node (ref "IC5") (pin "12") (pinfunction "+IN_12") (pintype "input"))
      (node (ref "R33") (pin "1") (pinfunction "1_1") (pintype "passive"))
    )
    (net (code "4") (name "FULL_WAVE_RECT") (class "Default")
      (node (ref "IC2") (pin "12") (pinfunction "+IN_12") (pintype "input"))
      (node (ref "IC2") (pin "8") (pinfunction "OUT_8") (pintype "output"))
      (node (ref "J7") (pin "P2") (pinfunction "2_P2") (pintype "passive"))
      (node (ref "R34") (pin "2") (pinfunction "2_2") (pintype "passive"))
      (node (ref "R36") (pin "1") (pinfunction "1_1") (pintype "passive"))
    )
    (net (code "5") (name "GND") (class "Default")
      (node (ref "C1") (pin "2") (pinfunction "2_2") (pintype "passive"))
      (node (ref "C12") (pin "1") (pinfunction "1_1") (pintype "passive"))
      (node (ref "C13") (pin "2") (pinfunction "2_2") (pintype "passive"))
      (node (ref "C14") (pin "2") (pinfunction "2_2") (pintype "passive"))
      (node (ref "C18") (pin "1") (pinfunction "1_1") (pintype "passive"))
      (node (ref "C19") (pin "2") (pinfunction "2_2") (pintype "passive"))
      (node (ref "C2") (pin "1") (pinfunction "1_1") (pintype "passive"))
      (node (ref "C20") (pin "1") (pinfunction "1_1") (pintype "passive"))
      (node (ref "C21") (pin "2") (pinfunction "2_2") (pintype "passive"))
      (node (ref "C3") (pin "2") (pinfunction "2_2") (pintype "passive"))
      (node (ref "C4") (pin "1") (pinfunction "1_1") (pintype "passive"))
      (node (ref "C55") (pin "2") (pinfunction "2_2") (pintype "passive"))
      (node (ref "C56") (pin "2") (pinfunction "2_2") (pintype "passive"))
      (node (ref "C58") (pin "-") (pinfunction "-_-") (pintype "passive"))
      (node (ref "C6") (pin "2") (pinfunction "2_2") (pintype "passive"))
      (node (ref "C8") (pin "2") (pinfunction "2_2") (pintype "passive"))
      (node (ref "C9") (pin "2") (pinfunction "2_2") (pintype "passive"))
      (node (ref "IC3") (pin "10") (pinfunction "+IN_10") (pintype "input"))
      (node (ref "IC3") (pin "3") (pinfunction "+IN_3") (pintype "input"))
      (node (ref "IC3") (pin "6") (pinfunction "-IN_6") (pintype "input"))
      (node (ref "IC4") (pin "4") (pinfunction "V-_4") (pintype "power_in"))
      (node (ref "IC6") (pin "2") (pinfunction "A_2") (pintype "passive"))
      (node (ref "J1") (pin "P1") (pinfunction "1_P1") (pintype "passive"))
      (node (ref "J10") (pin "P1") (pinfunction "1_P1") (pintype "passive"))
      (node (ref "J11") (pin "P1") (pinfunction "1_P1") (pintype "passive"))
      (node (ref "J2") (pin "P1") (pinfunction "1_P1") (pintype "passive"))
      (node (ref "J3") (pin "P1") (pinfunction "1_P1") (pintype "passive"))
      (node (ref "J4") (pin "P1") (pinfunction "1_P1") (pintype "passive"))
      (node (ref "J5") (pin "P1") (pinfunction "1_P1") (pintype "passive"))
      (node (ref "J6") (pin "P1") (pinfunction "1_P1") (pintype "passive"))
      (node (ref "J7") (pin "P1") (pinfunction "1_P1") (pintype "passive"))
      (node (ref "J8") (pin "P1") (pinfunction "1_P1") (pintype "passive"))
      (node (ref "J9") (pin "P1") (pinfunction "1_P1") (pintype "passive"))
      (node (ref "JP4") (pin "3") (pinfunction "3_3") (pintype "passive"))
      (node (ref "JP4") (pin "4") (pinfunction "4_4") (pintype "passive"))
      (node (ref "JP4") (pin "5") (pinfunction "5_5") (pintype "passive"))
      (node (ref "JP4") (pin "6") (pinfunction "6_6") (pintype "passive"))
      (node (ref "JP4") (pin "7") (pinfunction "7_7") (pintype "passive"))
      (node (ref "JP4") (pin "8") (pinfunction "8_8") (pintype "passive"))
      (node (ref "LED1") (pin "K") (pinfunction "C_K") (pintype "passive"))
      (node (ref "Q1") (pin "E") (pinfunction "E_E") (pintype "passive"))
      (node (ref "R10") (pin "1") (pinfunction "1_1") (pintype "passive"))
      (node (ref "R116") (pin "1") (pinfunction "1_1") (pintype "passive"))
      (node (ref "R117") (pin "1") (pinfunction "1_1") (pintype "passive"))
      (node (ref "R120") (pin "1") (pinfunction "1_1") (pintype "passive"))
      (node (ref "R30") (pin "1") (pinfunction "1_1") (pintype "passive"))
      (node (ref "R32") (pin "1") (pinfunction "1_1") (pintype "passive"))
      (node (ref "R5") (pin "1") (pinfunction "1_1") (pintype "passive"))
      (node (ref "R6") (pin "2") (pinfunction "2_2") (pintype "passive"))
      (node (ref "R8") (pin "2") (pinfunction "2_2") (pintype "passive"))
      (node (ref "R9") (pin "2") (pinfunction "2_2") (pintype "passive"))
    )
    (net (code "6") (name "LOWPASS") (class "Default")
      (node (ref "IC5") (pin "8") (pinfunction "OUT_8") (pintype "output"))
      (node (ref "IC5") (pin "9") (pinfunction "-IN_9") (pintype "input"))
      (node (ref "J11") (pin "P2") (pinfunction "2_P2") (pintype "passive"))
      (node (ref "R23") (pin "1") (pinfunction "1_1") (pintype "passive"))
    )
    (net (code "7") (name "Net-(C5-Pad2)") (class "Default")
      (node (ref "C5") (pin "2") (pinfunction "2_2") (pintype "passive"))
      (node (ref "R4") (pin "2") (pinfunction "2_2") (pintype "passive"))
      (node (ref "R5") (pin "2") (pinfunction "2_2") (pintype "passive"))
      (node (ref "SJ1") (pin "2") (pinfunction "2_2") (pintype "passive"))
    )
    (net (code "8") (name "Net-(C8-Pad1)") (class "Default")
      (node (ref "C8") (pin "1") (pinfunction "1_1") (pintype "passive"))
      (node (ref "D4") (pin "C") (pinfunction "C_C") (pintype "passive"))
      (node (ref "R11") (pin "2") (pinfunction "2_2") (pintype "passive"))
    )
    (net (code "9") (name "Net-(C16-Pad2)") (class "Default")
      (node (ref "C16") (pin "2") (pinfunction "2_2") (pintype "passive"))
      (node (ref "R1") (pin "1") (pinfunction "1_1") (pintype "passive"))
      (node (ref "SJ2") (pin "2") (pinfunction "2_2") (pintype "passive"))
    )
    (net (code "10") (name "Net-(C55-Pad1)") (class "Default")
      (node (ref "C55") (pin "1") (pinfunction "1_1") (pintype "passive"))
      (node (ref "R113") (pin "2") (pinfunction "2_2") (pintype "passive"))
      (node (ref "R114") (pin "1") (pinfunction "1_1") (pintype "passive"))
    )
    (net (code "11") (name "Net-(C57-Pad1)") (class "Default")
      (node (ref "C57") (pin "1") (pinfunction "1_1") (pintype "passive"))
      (node (ref "R115") (pin "1") (pinfunction "1_1") (pintype "passive"))
    )
    (net (code "12") (name "Net-(D1-PadA)") (class "Default")
      (node (ref "D1") (pin "A") (pinfunction "A_A") (pintype "passive"))
      (node (ref "JP4") (pin "1") (pinfunction "1_1") (pintype "passive"))
      (node (ref "JP4") (pin "2") (pinfunction "2_2") (pintype "passive"))
    )
    (net (code "13") (name "Net-(D1-PadC)") (class "Default")
      (node (ref "D1") (pin "C") (pinfunction "C_C") (pintype "passive"))
      (node (ref "L1") (pin "2") (pinfunction "2_2") (pintype "passive"))
    )
    (net (code "14") (name "Net-(D2-PadA)") (class "Default")
      (node (ref "D2") (pin "A") (pinfunction "A_A") (pintype "passive"))
      (node (ref "L2") (pin "2") (pinfunction "2_2") (pintype "passive"))
    )
    (net (code "15") (name "Net-(D2-PadC)") (class "Default")
      (node (ref "D2") (pin "C") (pinfunction "C_C") (pintype "passive"))
      (node (ref "JP4") (pin "10") (pinfunction "10_10") (pintype "passive"))
      (node (ref "JP4") (pin "9") (pinfunction "9_9") (pintype "passive"))
    )
    (net (code "16") (name "Net-(D13-PadC)") (class "Default")
      (node (ref "D13") (pin "C") (pinfunction "C_C") (pintype "passive"))
      (node (ref "D14") (pin "C") (pinfunction "C_C") (pintype "passive"))
      (node (ref "R113") (pin "1") (pinfunction "1_1") (pintype "passive"))
    )
    (net (code "17") (name "Net-(IC1A-+IN)") (class "Default")
      (node (ref "IC1") (pin "3") (pinfunction "+IN_3") (pintype "input"))
      (node (ref "R4") (pin "1") (pinfunction "1_1") (pintype "passive"))
    )
    (net (code "18") (name "Net-(IC1A--IN)") (class "Default")
      (node (ref "C7") (pin "1") (pinfunction "1_1") (pintype "passive"))
      (node (ref "IC1") (pin "2") (pinfunction "-IN_2") (pintype "input"))
      (node (ref "R6") (pin "1") (pinfunction "1_1") (pintype "passive"))
      (node (ref "R7") (pin "P$2") (pinfunction "S_P$2") (pintype "passive"))
    )
    (net (code "19") (name "Net-(IC2A-+IN)") (class "Default")
      (node (ref "C17") (pin "2") (pinfunction "2_2") (pintype "passive"))
      (node (ref "IC2") (pin "3") (pinfunction "+IN_3") (pintype "input"))
    )
    (net (code "20") (name "Net-(IC2A--IN)") (class "Default")
      (node (ref "IC2") (pin "1") (pinfunction "OUT_1") (pintype "output"))
      (node (ref "IC2") (pin "2") (pinfunction "-IN_2") (pintype "input"))
      (node (ref "IC2") (pin "5") (pinfunction "+IN_5") (pintype "input"))
      (node (ref "R30") (pin "2") (pinfunction "2_2") (pintype "passive"))
    )
    (net (code "21") (name "Net-(IC2B--IN)") (class "Default")
      (node (ref "C15") (pin "1") (pinfunction "1_1") (pintype "passive"))
      (node (ref "D7") (pin "A") (pinfunction "A_A") (pintype "passive"))
      (node (ref "IC2") (pin "6") (pinfunction "-IN_6") (pintype "input"))
      (node (ref "R31") (pin "1") (pinfunction "1_1") (pintype "passive"))
    )
    (net (code "22") (name "Net-(IC2B-OUT)") (class "Default")
      (node (ref "C15") (pin "2") (pinfunction "2_2") (pintype "passive"))
      (node (ref "D7") (pin "C") (pinfunction "C_C") (pintype "passive"))
      (node (ref "D8") (pin "A") (pinfunction "A_A") (pintype "passive"))
      (node (ref "IC2") (pin "7") (pinfunction "OUT_7") (pintype "output"))
    )
    (net (code "23") (name "Net-(IC2C-+IN)") (class "Default")
      (node (ref "D8") (pin "C") (pinfunction "C_C") (pintype "passive"))
      (node (ref "IC2") (pin "10") (pinfunction "+IN_10") (pintype "input"))
      (node (ref "R32") (pin "2") (pinfunction "2_2") (pintype "passive"))
    )
    (net (code "24") (name "Net-(IC2C--IN)") (class "Default")
      (node (ref "IC2") (pin "9") (pinfunction "-IN_9") (pintype "input"))
      (node (ref "R31") (pin "2") (pinfunction "2_2") (pintype "passive"))
      (node (ref "R34") (pin "1") (pinfunction "1_1") (pintype "passive"))
    )
    (net (code "25") (name "Net-(IC2D-OUT)") (class "Default")
      (node (ref "D4") (pin "A") (pinfunction "A_A") (pintype "passive"))
      (node (ref "IC2") (pin "14") (pinfunction "OUT_14") (pintype "output"))
    )
    (net (code "26") (name "Net-(IC3A--IN)") (class "Default")
      (node (ref "IC3") (pin "2") (pinfunction "-IN_2") (pintype "input"))
      (node (ref "R25") (pin "2") (pinfunction "2_2") (pintype "passive"))
      (node (ref "R29") (pin "1") (pinfunction "1_1") (pintype "passive"))
    )
    (net (code "27") (name "Net-(IC3A-OUT)") (class "Default")
      (node (ref "IC3") (pin "1") (pinfunction "OUT_1") (pintype "output"))
      (node (ref "R26") (pin "1") (pinfunction "1_1") (pintype "passive"))
      (node (ref "R29") (pin "2") (pinfunction "2_2") (pintype "passive"))
    )
    (net (code "28") (name "Net-(IC3B-+IN)") (class "Default")
      (node (ref "IC3") (pin "5") (pinfunction "+IN_5") (pintype "input"))
      (node (ref "R26") (pin "2") (pinfunction "2_2") (pintype "passive"))
      (node (ref "R28") (pin "1") (pinfunction "1_1") (pintype "passive"))
    )
    (net (code "29") (name "Net-(IC3B-OUT)") (class "Default")
      (node (ref "D5") (pin "A") (pinfunction "A_A") (pintype "passive"))
      (node (ref "D6") (pin "C") (pinfunction "C_C") (pintype "passive"))
      (node (ref "IC3") (pin "7") (pinfunction "OUT_7") (pintype "output"))
    )
    (net (code "30") (name "Net-(IC3C--IN)") (class "Default")
      (node (ref "C11") (pin "1") (pinfunction "1_1") (pintype "passive"))
      (node (ref "IC3") (pin "9") (pinfunction "-IN_9") (pintype "input"))
      (node (ref "R18") (pin "P$2") (pinfunction "S_P$2") (pintype "passive"))
      (node (ref "R19") (pin "P$2") (pinfunction "S_P$2") (pintype "passive"))
    )
    (net (code "31") (name "Net-(IC3D-+IN)") (class "Default")
      (node (ref "IC3") (pin "12") (pinfunction "+IN_12") (pintype "input"))
      (node (ref "R13") (pin "2") (pinfunction "2_2") (pintype "passive"))
    )
    (net (code "32") (name "Net-(IC3D--IN)") (class "Default")
      (node (ref "IC3") (pin "13") (pinfunction "-IN_13") (pintype "input"))
      (node (ref "IC3") (pin "14") (pinfunction "OUT_14") (pintype "output"))
      (node (ref "R25") (pin "1") (pinfunction "1_1") (pintype "passive"))
    )
    (net (code "33") (name "Net-(IC4A-+IN)") (class "Default")
      (node (ref "IC4") (pin "3") (pinfunction "+IN_3") (pintype "input"))
      (node (ref "IC4") (pin "6") (pinfunction "-IN_6") (pintype "input"))
      (node (ref "R115") (pin "2") (pinfunction "2_2") (pintype "passive"))
      (node (ref "R117") (pin "2") (pinfunction "2_2") (pintype "passive"))
      (node (ref "R118") (pin "1") (pinfunction "1_1") (pintype "passive"))
    )
    (net (code "34") (name "Net-(IC4A--IN)") (class "Default")
      (node (ref "IC4") (pin "2") (pinfunction "-IN_2") (pintype "input"))
      (node (ref "R119") (pin "2") (pinfunction "2_2") (pintype "passive"))
      (node (ref "R121") (pin "1") (pinfunction "1_1") (pintype "passive"))
    )
    (net (code "35") (name "Net-(IC4A-OUT)") (class "Default")
      (node (ref "D13") (pin "A") (pinfunction "A_A") (pintype "passive"))
      (node (ref "IC4") (pin "1") (pinfunction "OUT_1") (pintype "output"))
    )
    (net (code "36") (name "Net-(IC4B-+IN)") (class "Default")
      (node (ref "IC4") (pin "5") (pinfunction "+IN_5") (pintype "input"))
      (node (ref "R119") (pin "1") (pinfunction "1_1") (pintype "passive"))
      (node (ref "R120") (pin "2") (pinfunction "2_2") (pintype "passive"))
    )
    (net (code "37") (name "Net-(IC4B-OUT)") (class "Default")
      (node (ref "D14") (pin "A") (pinfunction "A_A") (pintype "passive"))
      (node (ref "IC4") (pin "7") (pinfunction "OUT_7") (pintype "output"))
    )
    (net (code "38") (name "Net-(IC5A--IN)") (class "Default")
      (node (ref "IC5") (pin "2") (pinfunction "-IN_2") (pintype "input"))
      (node (ref "LED2") (pin "K") (pinfunction "C_K") (pintype "passive"))
      (node (ref "R9") (pin "1") (pinfunction "1_1") (pintype "passive"))
    )
    (net (code "39") (name "Net-(IC5A-OUT)") (class "Default")
      (node (ref "IC5") (pin "1") (pinfunction "OUT_1") (pintype "output"))
      (node (ref "LED2") (pin "A") (pinfunction "A_A") (pintype "passive"))
    )
    (net (code "40") (name "Net-(IC5B-+IN)") (class "Default")
      (node (ref "IC5") (pin "5") (pinfunction "+IN_5") (pintype "input"))
      (node (ref "R14") (pin "2") (pinfunction "2_2") (pintype "passive"))
    )
    (net (code "41") (name "Net-(IC5B--IN)") (class "Default")
      (node (ref "IC5") (pin "6") (pinfunction "-IN_6") (pintype "input"))
      (node (ref "IC5") (pin "7") (pinfunction "OUT_7") (pintype "output"))
      (node (ref "R12") (pin "P$2") (pinfunction "S_P$2") (pintype "passive"))
    )
    (net (code "42") (name "Net-(IC5C-+IN)") (class "Default")
      (node (ref "C21") (pin "1") (pinfunction "1_1") (pintype "passive"))
      (node (ref "IC5") (pin "10") (pinfunction "+IN_10") (pintype "input"))
      (node (ref "R12") (pin "P$3") (pinfunction "A_P$3") (pintype "passive"))
    )
    (net (code "43") (name "Net-(IC5D--IN)") (class "Default")
      (node (ref "IC5") (pin "13") (pinfunction "-IN_13") (pintype "input"))
      (node (ref "LED3") (pin "K") (pinfunction "C_K") (pintype "passive"))
      (node (ref "R10") (pin "2") (pinfunction "2_2") (pintype "passive"))
    )
    (net (code "44") (name "Net-(IC5D-OUT)") (class "Default")
      (node (ref "IC5") (pin "14") (pinfunction "OUT_14") (pintype "output"))
      (node (ref "LED3") (pin "A") (pinfunction "A_A") (pintype "passive"))
    )
    (net (code "45") (name "Net-(J1-3)") (class "Default")
      (node (ref "C3") (pin "1") (pinfunction "1_1") (pintype "passive"))
      (node (ref "C5") (pin "1") (pinfunction "1_1") (pintype "passive"))
      (node (ref "J1") (pin "P3") (pinfunction "3_P3") (pintype "passive"))
      (node (ref "SJ1") (pin "1") (pinfunction "1_1") (pintype "passive"))
    )
    (net (code "46") (name "Net-(J2-3)") (class "Default")
      (node (ref "J2") (pin "P3") (pinfunction "3_P3") (pintype "passive"))
      (node (ref "R1") (pin "2") (pinfunction "2_2") (pintype "passive"))
    )
    (net (code "47") (name "Net-(J3-3)") (class "Default")
      (node (ref "J3") (pin "P3") (pinfunction "3_P3") (pintype "passive"))
      (node (ref "R2") (pin "2") (pinfunction "2_2") (pintype "passive"))
    )
    (net (code "48") (name "Net-(J4-3)") (class "Default")
      (node (ref "J4") (pin "P3") (pinfunction "3_P3") (pintype "passive"))
      (node (ref "R23") (pin "2") (pinfunction "2_2") (pintype "passive"))
    )
    (net (code "49") (name "Net-(J5-3)") (class "Default")
      (node (ref "J5") (pin "P3") (pinfunction "3_P3") (pintype "passive"))
      (node (ref "R36") (pin "2") (pinfunction "2_2") (pintype "passive"))
    )
    (net (code "50") (name "Net-(J6-3)") (class "Default")
      (node (ref "C17") (pin "1") (pinfunction "1_1") (pintype "passive"))
      (node (ref "J6") (pin "P3") (pinfunction "3_P3") (pintype "passive"))
    )
    (net (code "51") (name "Net-(J7-3)") (class "Default")
      (node (ref "J7") (pin "P3") (pinfunction "3_P3") (pintype "passive"))
      (node (ref "R13") (pin "1") (pinfunction "1_1") (pintype "passive"))
    )
    (net (code "52") (name "Net-(J8-3)") (class "Default")
      (node (ref "J8") (pin "P3") (pinfunction "3_P3") (pintype "passive"))
      (node (ref "R14") (pin "1") (pinfunction "1_1") (pintype "passive"))
    )
    (net (code "53") (name "Net-(J9-3)") (class "Default")
      (node (ref "J9") (pin "P3") (pinfunction "3_P3") (pintype "passive"))
      (node (ref "R33") (pin "2") (pinfunction "2_2") (pintype "passive"))
    )
    (net (code "54") (name "Net-(J10-3)") (class "Default")
      (node (ref "J10") (pin "P3") (pinfunction "3_P3") (pintype "passive"))
      (node (ref "R16") (pin "1") (pinfunction "1_1") (pintype "passive"))
    )
    (net (code "55") (name "Net-(J11-3)") (class "Default")
      (node (ref "J11") (pin "P3") (pinfunction "3_P3") (pintype "passive"))
      (node (ref "R15") (pin "1") (pinfunction "1_1") (pintype "passive"))
    )
    (net (code "56") (name "Net-(LED1-PadA)") (class "Default")
      (node (ref "LED1") (pin "A") (pinfunction "A_A") (pintype "passive"))
      (node (ref "R11") (pin "1") (pinfunction "1_1") (pintype "passive"))
    )
    (net (code "57") (name "Net-(LED4-C)") (class "Default")
      (node (ref "LED4") (pin "K") (pinfunction "C_K") (pintype "passive"))
      (node (ref "Q1") (pin "C") (pinfunction "C_C") (pintype "passive"))
    )
    (net (code "58") (name "Net-(LED4-PadA)") (class "Default")
      (node (ref "LED4") (pin "A") (pinfunction "A_A") (pintype "passive"))
      (node (ref "R112") (pin "1") (pinfunction "1_1") (pintype "passive"))
    )
    (net (code "59") (name "Net-(Q1-PadB)") (class "Default")
      (node (ref "Q1") (pin "B") (pinfunction "B_B") (pintype "passive"))
      (node (ref "R114") (pin "2") (pinfunction "2_2") (pintype "passive"))
      (node (ref "R116") (pin "2") (pinfunction "2_2") (pintype "passive"))
    )
    (net (code "60") (name "Net-(R7-E)") (class "Default")
      (node (ref "R7") (pin "P$1") (pinfunction "E_P$1") (pintype "passive"))
      (node (ref "R8") (pin "1") (pinfunction "1_1") (pintype "passive"))
    )
    (net (code "61") (name "Net-(R18-A)") (class "Default")
      (node (ref "D6") (pin "A") (pinfunction "A_A") (pintype "passive"))
      (node (ref "R18") (pin "P$3") (pinfunction "A_P$3") (pintype "passive"))
    )
    (net (code "62") (name "Net-(R19-A)") (class "Default")
      (node (ref "D5") (pin "C") (pinfunction "C_C") (pintype "passive"))
      (node (ref "R19") (pin "P$3") (pinfunction "A_P$3") (pintype "passive"))
    )
    (net (code "63") (name "SLEW") (class "Default")
      (node (ref "C11") (pin "2") (pinfunction "2_2") (pintype "passive"))
      (node (ref "IC3") (pin "8") (pinfunction "OUT_8") (pintype "output"))
      (node (ref "IC5") (pin "3") (pinfunction "+IN_3") (pintype "input"))
      (node (ref "J8") (pin "P2") (pinfunction "2_P2") (pintype "passive"))
      (node (ref "R2") (pin "1") (pinfunction "1_1") (pintype "passive"))
      (node (ref "R28") (pin "2") (pinfunction "2_2") (pintype "passive"))
    )
    (net (code "64") (name "THRESH") (class "Default")
      (node (ref "J10") (pin "P2") (pinfunction "2_P2") (pintype "passive"))
    )
    (net (code "65") (name "VCC") (class "Default")
      (node (ref "C1") (pin "1") (pinfunction "1_1") (pintype "passive"))
      (node (ref "C13") (pin "1") (pinfunction "1_1") (pintype "passive"))
      (node (ref "C19") (pin "1") (pinfunction "1_1") (pintype "passive"))
      (node (ref "C56") (pin "1") (pinfunction "1_1") (pintype "passive"))
      (node (ref "C58") (pin "+") (pinfunction "+_+") (pintype "passive"))
      (node (ref "C6") (pin "1") (pinfunction "1_1") (pintype "passive"))
      (node (ref "C9") (pin "1") (pinfunction "1_1") (pintype "passive"))
      (node (ref "IC1") (pin "7") (pinfunction "V+_7") (pintype "power_in"))
      (node (ref "IC2") (pin "4") (pinfunction "V+_4") (pintype "power_in"))
      (node (ref "IC3") (pin "4") (pinfunction "V+_4") (pintype "power_in"))
      (node (ref "IC4") (pin "8") (pinfunction "V+_8") (pintype "power_in"))
      (node (ref "IC5") (pin "4") (pinfunction "V+_4") (pintype "power_in"))
      (node (ref "L1") (pin "1") (pinfunction "1_1") (pintype "passive"))
      (node (ref "R112") (pin "2") (pinfunction "2_2") (pintype "passive"))
      (node (ref "R3") (pin "1") (pinfunction "1_1") (pintype "passive"))
    )
    (net (code "66") (name "VEE") (class "Default")
      (node (ref "C12") (pin "2") (pinfunction "2_2") (pintype "passive"))
      (node (ref "C18") (pin "2") (pinfunction "2_2") (pintype "passive"))
      (node (ref "C2") (pin "2") (pinfunction "2_2") (pintype "passive"))
      (node (ref "C20") (pin "2") (pinfunction "2_2") (pintype "passive"))
      (node (ref "C4") (pin "2") (pinfunction "2_2") (pintype "passive"))
      (node (ref "IC1") (pin "4") (pinfunction "V-_4") (pintype "power_in"))
      (node (ref "IC2") (pin "11") (pinfunction "V-_11") (pintype "power_in"))
      (node (ref "IC3") (pin "11") (pinfunction "V-_11") (pintype "power_in"))
      (node (ref "IC5") (pin "11") (pinfunction "V-_11") (pintype "power_in"))
      (node (ref "L2") (pin "1") (pinfunction "1_1") (pintype "passive"))
    )
    (net (code "67") (name "unconnected-(C10-Pad1)") (class "Default")
      (node (ref "C10") (pin "1") (pinfunction "1_1") (pintype "passive"))
    )
    (net (code "68") (name "unconnected-(C10-Pad2)") (class "Default")
      (node (ref "C10") (pin "2") (pinfunction "2_2") (pintype "passive"))
    )
    (net (code "69") (name "unconnected-(J1-2-PadP2)") (class "Default")
      (node (ref "J1") (pin "P2") (pinfunction "2_P2") (pintype "passive"))
    )
    (net (code "70") (name "unconnected-(J2-2-PadP2)") (class "Default")
      (node (ref "J2") (pin "P2") (pinfunction "2_P2") (pintype "passive"))
    )
    (net (code "71") (name "unconnected-(J3-2-PadP2)") (class "Default")
      (node (ref "J3") (pin "P2") (pinfunction "2_P2") (pintype "passive"))
    )
    (net (code "72") (name "unconnected-(J4-2-PadP2)") (class "Default")
      (node (ref "J4") (pin "P2") (pinfunction "2_P2") (pintype "passive"))
    )
    (net (code "73") (name "unconnected-(J5-2-PadP2)") (class "Default")
      (node (ref "J5") (pin "P2") (pinfunction "2_P2") (pintype "passive"))
    )
    (net (code "74") (name "unconnected-(J9-2-PadP2)") (class "Default")
      (node (ref "J9") (pin "P2") (pinfunction "2_P2") (pintype "passive"))
    )
    (net (code "75") (name "unconnected-(R12-E-PadP$1)") (class "Default")
      (node (ref "R12") (pin "P$1") (pinfunction "E_P$1") (pintype "passive"))
    )
    (net (code "76") (name "unconnected-(R15-Pad2)") (class "Default")
      (node (ref "R15") (pin "2") (pinfunction "2_2") (pintype "passive"))
    )
    (net (code "77") (name "unconnected-(R16-Pad2)") (class "Default")
      (node (ref "R16") (pin "2") (pinfunction "2_2") (pintype "passive"))
    )
    (net (code "78") (name "unconnected-(R18-E-PadP$1)") (class "Default")
      (node (ref "R18") (pin "P$1") (pinfunction "E_P$1") (pintype "passive"))
    )
    (net (code "79") (name "unconnected-(R19-E-PadP$1)") (class "Default")
      (node (ref "R19") (pin "P$1") (pinfunction "E_P$1") (pintype "passive"))
    )
  )
)
